# AD5940.net
KiCad netlist of a schematic drawn in Altium Designer
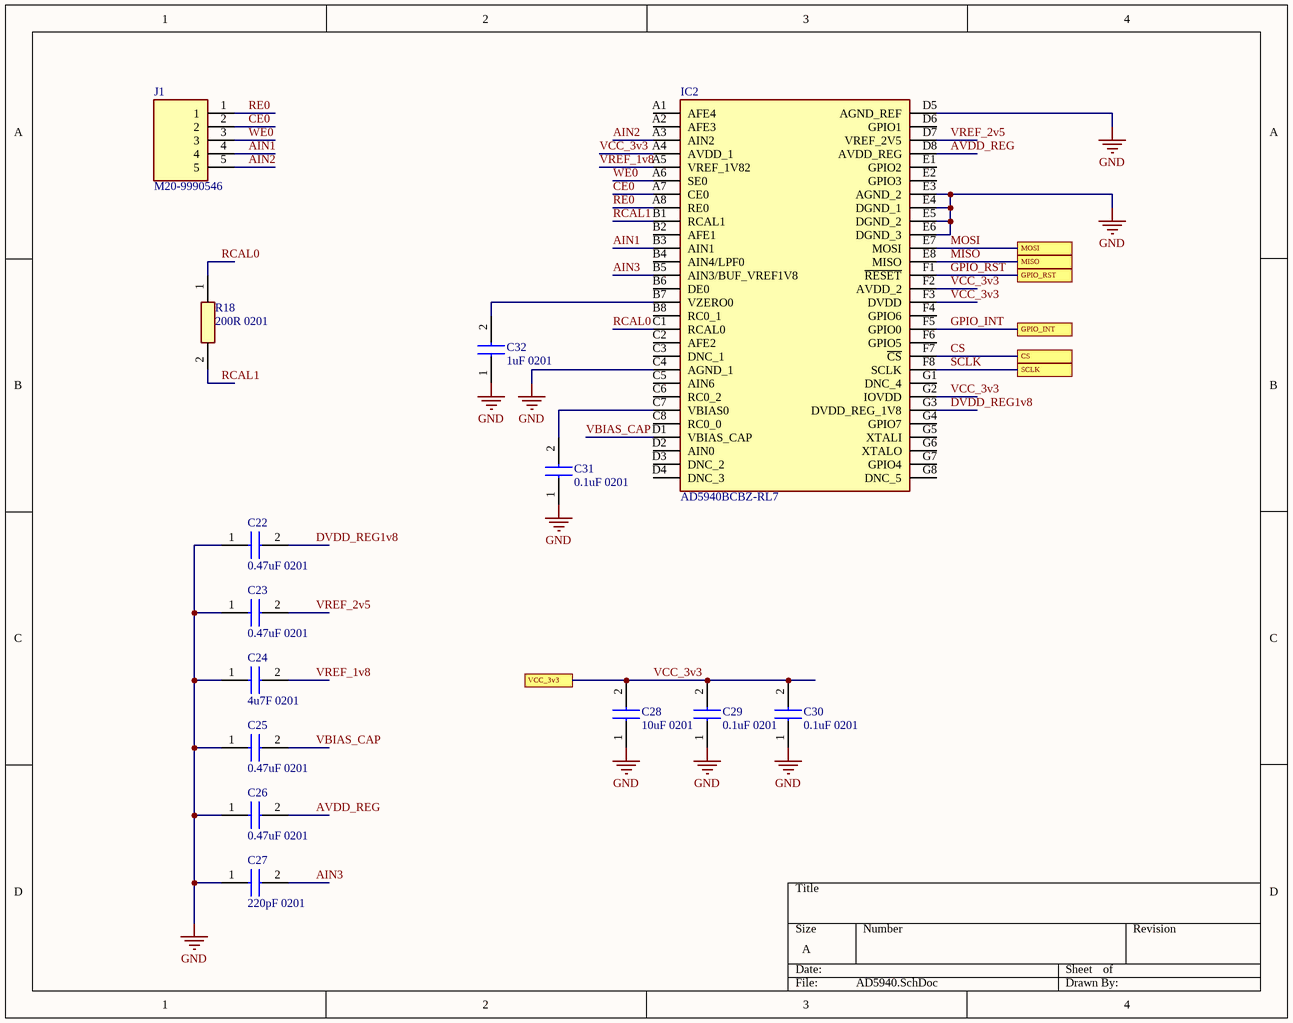
[diagram p0: AD5940.SchDoc]

(export (version "E")
  (design (tool "Eeschema 10.0.6"))
  (components
    (comp (ref "C22")
      (value "0.47uF 0201")
      (footprint "SamacSys:CAPC0603X33N")
      (description "Capacitor")
      (fields
        (field (name "MANUFACTURER_PART_NUMBER") "02013A0R5BAT2A")
        (field (name "MOUSER PART NUMBER") "581-02013A0R5BAT2A")
      )
      (libsource (lib "*") (part "02013A0R5BAT2A"))
    )
    (comp (ref "C23")
      (value "0.47uF 0201")
      (footprint "SamacSys:CAPC0603X33N")
      (description "Capacitor")
      (fields
        (field (name "MANUFACTURER_PART_NUMBER") "02013A0R5BAT2A")
        (field (name "MOUSER PART NUMBER") "581-02013A0R5BAT2A")
      )
      (libsource (lib "*") (part "02013A0R5BAT2A"))
    )
    (comp (ref "C24")
      (value "4u7F 0201")
      (footprint "SamacSys:CAPC0603X33N")
      (description "Capacitor")
      (fields
        (field (name "MANUFACTURER_PART_NUMBER") "02013A0R5BAT2A")
        (field (name "MOUSER PART NUMBER") "581-02013A0R5BAT2A")
      )
      (libsource (lib "*") (part "02013A0R5BAT2A"))
    )
    (comp (ref "C25")
      (value "0.47uF 0201")
      (footprint "SamacSys:CAPC0603X33N")
      (description "Capacitor")
      (fields
        (field (name "MANUFACTURER_PART_NUMBER") "02013A0R5BAT2A")
        (field (name "MOUSER PART NUMBER") "581-02013A0R5BAT2A")
      )
      (libsource (lib "*") (part "02013A0R5BAT2A"))
    )
    (comp (ref "C26")
      (value "0.47uF 0201")
      (footprint "SamacSys:CAPC0603X33N")
      (description "Capacitor")
      (fields
        (field (name "MANUFACTURER_PART_NUMBER") "02013A0R5BAT2A")
        (field (name "MOUSER PART NUMBER") "581-02013A0R5BAT2A")
      )
      (libsource (lib "*") (part "02013A0R5BAT2A"))
    )
    (comp (ref "C27")
      (value "220pF 0201")
      (footprint "SamacSys:CAPC0603X33N")
      (description "Capacitor")
      (fields
        (field (name "MANUFACTURER_PART_NUMBER") "02013A0R5BAT2A")
        (field (name "MOUSER PART NUMBER") "581-02013A0R5BAT2A")
      )
      (libsource (lib "*") (part "02013A0R5BAT2A"))
    )
    (comp (ref "C28")
      (value "10uF 0201")
      (footprint "SamacSys:CAPC0603X33N")
      (description "Capacitor")
      (fields
        (field (name "MANUFACTURER_PART_NUMBER") "02013A0R5BAT2A")
        (field (name "MOUSER PART NUMBER") "581-02013A0R5BAT2A")
      )
      (libsource (lib "*") (part "02013A0R5BAT2A"))
    )
    (comp (ref "C29")
      (value "0.1uF 0201")
      (footprint "SamacSys:CAPC0603X33N")
      (description "Capacitor")
      (fields
        (field (name "MANUFACTURER_PART_NUMBER") "02013A0R5BAT2A")
        (field (name "MOUSER PART NUMBER") "581-02013A0R5BAT2A")
      )
      (libsource (lib "*") (part "02013A0R5BAT2A"))
    )
    (comp (ref "C30")
      (value "0.1uF 0201")
      (footprint "SamacSys:CAPC0603X33N")
      (description "Capacitor")
      (fields
        (field (name "MANUFACTURER_PART_NUMBER") "02013A0R5BAT2A")
        (field (name "MOUSER PART NUMBER") "581-02013A0R5BAT2A")
      )
      (libsource (lib "*") (part "02013A0R5BAT2A"))
    )
    (comp (ref "C31")
      (value "0.1uF 0201")
      (footprint "SamacSys:CAPC0603X33N")
      (description "Capacitor")
      (fields
        (field (name "MANUFACTURER_PART_NUMBER") "02013A0R5BAT2A")
        (field (name "MOUSER PART NUMBER") "581-02013A0R5BAT2A")
      )
      (libsource (lib "*") (part "02013A0R5BAT2A"))
    )
    (comp (ref "C32")
      (value "1uF 0201")
      (footprint "SamacSys:CAPC0603X33N")
      (description "Capacitor")
      (fields
        (field (name "MANUFACTURER_PART_NUMBER") "02013A0R5BAT2A")
        (field (name "MOUSER PART NUMBER") "581-02013A0R5BAT2A")
      )
      (libsource (lib "*") (part "02013A0R5BAT2A"))
    )
    (comp (ref "IC2")
      (value "AD5940BCBZ-RL7")
      (footprint "SamacSys:BGA56C40P8X7_416X356X55")
      (description "Integrated Circuit")
      (fields (field (name "MOUSER PART NUMBER") "584-AD5940BCBZ-RL7"))
      (libsource (lib "*") (part "AD5940BCBZ-RL7"))
    )
    (comp (ref "J1")
      (value "M20-9990546")
      (footprint "SamacSys:HDRV5W64P0X254_1X5_1270X254X610P")
      (description "Connector")
      (fields (field (name "MOUSER PART NUMBER") "855-M20-9990546"))
      (libsource (lib "*") (part "M20-9990546"))
    )
    (comp (ref "R18")
      (value "200R 0201")
      (footprint "SamacSys:RESC0603X28N")
      (description "Resistor")
      (fields (field (name "MANUFACTURER_PART_NUMBER") "CPF0201D422RE1"))
      (libsource (lib "*") (part "CPF0201D422RE1"))
    )
  )
  (nets
    (net (code "1") (name "/AIN1") (class "Default")
      (node (ref "IC2") (pin "B3") (pinfunction "AIN1_B3") (pintype "passive"))
      (node (ref "J1") (pin "4") (pinfunction "4_4") (pintype "passive"))
    )
    (net (code "2") (name "/AIN2") (class "Default")
      (node (ref "IC2") (pin "A3") (pinfunction "AIN2_A3") (pintype "passive"))
      (node (ref "J1") (pin "5") (pinfunction "5_5") (pintype "passive"))
    )
    (net (code "3") (name "/AIN3") (class "Default")
      (node (ref "C27") (pin "2") (pinfunction "2_2") (pintype "passive"))
      (node (ref "IC2") (pin "B5") (pinfunction "AIN3/BUF_VREF1V8_B5") (pintype "passive"))
    )
    (net (code "4") (name "/AVDD_REG") (class "Default")
      (node (ref "C26") (pin "2") (pinfunction "2_2") (pintype "passive"))
      (node (ref "IC2") (pin "D8") (pinfunction "AVDD_REG_D8") (pintype "passive"))
    )
    (net (code "5") (name "/CE0") (class "Default")
      (node (ref "IC2") (pin "A7") (pinfunction "CE0_A7") (pintype "passive"))
      (node (ref "J1") (pin "2") (pinfunction "2_2") (pintype "passive"))
    )
    (net (code "6") (name "/CS") (class "Default")
      (node (ref "IC2") (pin "F7") (pinfunction "~{CS}_F7") (pintype "passive"))
    )
    (net (code "7") (name "/DVDD_REG1v8") (class "Default")
      (node (ref "C22") (pin "2") (pinfunction "2_2") (pintype "passive"))
      (node (ref "IC2") (pin "G3") (pinfunction "DVDD_REG_1V8_G3") (pintype "passive"))
    )
    (net (code "8") (name "/GPIO_INT") (class "Default")
      (node (ref "IC2") (pin "F5") (pinfunction "GPIO0_F5") (pintype "passive"))
    )
    (net (code "9") (name "/GPIO_RST") (class "Default")
      (node (ref "IC2") (pin "F1") (pinfunction "~{RESET}_F1") (pintype "passive"))
    )
    (net (code "10") (name "/MISO") (class "Default")
      (node (ref "IC2") (pin "E8") (pinfunction "MISO_E8") (pintype "passive"))
    )
    (net (code "11") (name "/MOSI") (class "Default")
      (node (ref "IC2") (pin "E7") (pinfunction "MOSI_E7") (pintype "passive"))
    )
    (net (code "12") (name "/RCAL0") (class "Default")
      (node (ref "IC2") (pin "C1") (pinfunction "RCAL0_C1") (pintype "passive"))
      (node (ref "R18") (pin "1") (pinfunction "1_1") (pintype "passive"))
    )
    (net (code "13") (name "/RCAL1") (class "Default")
      (node (ref "IC2") (pin "B1") (pinfunction "RCAL1_B1") (pintype "passive"))
      (node (ref "R18") (pin "2") (pinfunction "2_2") (pintype "passive"))
    )
    (net (code "14") (name "/RE0") (class "Default")
      (node (ref "IC2") (pin "A8") (pinfunction "RE0_A8") (pintype "passive"))
      (node (ref "J1") (pin "1") (pinfunction "1_1") (pintype "passive"))
    )
    (net (code "15") (name "/SCLK") (class "Default")
      (node (ref "IC2") (pin "F8") (pinfunction "SCLK_F8") (pintype "passive"))
    )
    (net (code "16") (name "/VBIAS_CAP") (class "Default")
      (node (ref "C25") (pin "2") (pinfunction "2_2") (pintype "passive"))
      (node (ref "IC2") (pin "D1") (pinfunction "VBIAS_CAP_D1") (pintype "passive"))
    )
    (net (code "17") (name "/VCC_3v3") (class "Default")
      (node (ref "C28") (pin "2") (pinfunction "2_2") (pintype "passive"))
      (node (ref "C29") (pin "2") (pinfunction "2_2") (pintype "passive"))
      (node (ref "C30") (pin "2") (pinfunction "2_2") (pintype "passive"))
      (node (ref "IC2") (pin "A4") (pinfunction "AVDD_1_A4") (pintype "passive"))
      (node (ref "IC2") (pin "F2") (pinfunction "AVDD_2_F2") (pintype "passive"))
      (node (ref "IC2") (pin "F3") (pinfunction "DVDD_F3") (pintype "passive"))
      (node (ref "IC2") (pin "G2") (pinfunction "IOVDD_G2") (pintype "passive"))
    )
    (net (code "18") (name "/VREF_1v8") (class "Default")
      (node (ref "C24") (pin "2") (pinfunction "2_2") (pintype "passive"))
      (node (ref "IC2") (pin "A5") (pinfunction "VREF_1V82_A5") (pintype "passive"))
    )
    (net (code "19") (name "/VREF_2v5") (class "Default")
      (node (ref "C23") (pin "2") (pinfunction "2_2") (pintype "passive"))
      (node (ref "IC2") (pin "D7") (pinfunction "VREF_2V5_D7") (pintype "passive"))
    )
    (net (code "20") (name "/WE0") (class "Default")
      (node (ref "IC2") (pin "A6") (pinfunction "SE0_A6") (pintype "passive"))
      (node (ref "J1") (pin "3") (pinfunction "3_3") (pintype "passive"))
    )
    (net (code "21") (name "GND") (class "Default")
      (node (ref "C22") (pin "1") (pinfunction "1_1") (pintype "passive"))
      (node (ref "C23") (pin "1") (pinfunction "1_1") (pintype "passive"))
      (node (ref "C24") (pin "1") (pinfunction "1_1") (pintype "passive"))
      (node (ref "C25") (pin "1") (pinfunction "1_1") (pintype "passive"))
      (node (ref "C26") (pin "1") (pinfunction "1_1") (pintype "passive"))
      (node (ref "C27") (pin "1") (pinfunction "1_1") (pintype "passive"))
      (node (ref "C28") (pin "1") (pinfunction "1_1") (pintype "passive"))
      (node (ref "C29") (pin "1") (pinfunction "1_1") (pintype "passive"))
      (node (ref "C30") (pin "1") (pinfunction "1_1") (pintype "passive"))
      (node (ref "C31") (pin "1") (pinfunction "1_1") (pintype "passive"))
      (node (ref "C32") (pin "1") (pinfunction "1_1") (pintype "passive"))
      (node (ref "IC2") (pin "C4") (pinfunction "AGND_1_C4") (pintype "passive"))
      (node (ref "IC2") (pin "D5") (pinfunction "AGND_REF_D5") (pintype "passive"))
      (node (ref "IC2") (pin "E3") (pinfunction "AGND_2_E3") (pintype "passive"))
      (node (ref "IC2") (pin "E4") (pinfunction "DGND_1_E4") (pintype "passive"))
      (node (ref "IC2") (pin "E5") (pinfunction "DGND_2_E5") (pintype "passive"))
      (node (ref "IC2") (pin "E6") (pinfunction "DGND_3_E6") (pintype "passive"))
    )
    (net (code "22") (name "Net-(IC2-VBIAS0)") (class "Default")
      (node (ref "C31") (pin "2") (pinfunction "2_2") (pintype "passive"))
      (node (ref "IC2") (pin "C7") (pinfunction "VBIAS0_C7") (pintype "passive"))
    )
    (net (code "23") (name "Net-(IC2-VZERO0)") (class "Default")
      (node (ref "C32") (pin "2") (pinfunction "2_2") (pintype "passive"))
      (node (ref "IC2") (pin "B7") (pinfunction "VZERO0_B7") (pintype "passive"))
    )
    (net (code "24") (name "unconnected-(IC2-AFE1-PadB2)") (class "Default")
      (node (ref "IC2") (pin "B2") (pinfunction "AFE1_B2") (pintype "passive"))
    )
    (net (code "25") (name "unconnected-(IC2-AFE2-PadC2)") (class "Default")
      (node (ref "IC2") (pin "C2") (pinfunction "AFE2_C2") (pintype "passive"))
    )
    (net (code "26") (name "unconnected-(IC2-AFE3-PadA2)") (class "Default")
      (node (ref "IC2") (pin "A2") (pinfunction "AFE3_A2") (pintype "passive"))
    )
    (net (code "27") (name "unconnected-(IC2-AFE4-PadA1)") (class "Default")
      (node (ref "IC2") (pin "A1") (pinfunction "AFE4_A1") (pintype "passive"))
    )
    (net (code "28") (name "unconnected-(IC2-AIN0-PadD2)") (class "Default")
      (node (ref "IC2") (pin "D2") (pinfunction "AIN0_D2") (pintype "passive"))
    )
    (net (code "29") (name "unconnected-(IC2-AIN4{slash}LPF0-PadB4)") (class "Default")
      (node (ref "IC2") (pin "B4") (pinfunction "AIN4/LPF0_B4") (pintype "passive"))
    )
    (net (code "30") (name "unconnected-(IC2-AIN6-PadC5)") (class "Default")
      (node (ref "IC2") (pin "C5") (pinfunction "AIN6_C5") (pintype "passive"))
    )
    (net (code "31") (name "unconnected-(IC2-DE0-PadB6)") (class "Default")
      (node (ref "IC2") (pin "B6") (pinfunction "DE0_B6") (pintype "passive"))
    )
    (net (code "32") (name "unconnected-(IC2-DNC_1-PadC3)") (class "Default")
      (node (ref "IC2") (pin "C3") (pinfunction "DNC_1_C3") (pintype "passive"))
    )
    (net (code "33") (name "unconnected-(IC2-DNC_2-PadD3)") (class "Default")
      (node (ref "IC2") (pin "D3") (pinfunction "DNC_2_D3") (pintype "passive"))
    )
    (net (code "34") (name "unconnected-(IC2-DNC_3-PadD4)") (class "Default")
      (node (ref "IC2") (pin "D4") (pinfunction "DNC_3_D4") (pintype "passive"))
    )
    (net (code "35") (name "unconnected-(IC2-DNC_4-PadG1)") (class "Default")
      (node (ref "IC2") (pin "G1") (pinfunction "DNC_4_G1") (pintype "passive"))
    )
    (net (code "36") (name "unconnected-(IC2-DNC_5-PadG8)") (class "Default")
      (node (ref "IC2") (pin "G8") (pinfunction "DNC_5_G8") (pintype "passive"))
    )
    (net (code "37") (name "unconnected-(IC2-GPIO1-PadD6)") (class "Default")
      (node (ref "IC2") (pin "D6") (pinfunction "GPIO1_D6") (pintype "passive"))
    )
    (net (code "38") (name "unconnected-(IC2-GPIO2-PadE1)") (class "Default")
      (node (ref "IC2") (pin "E1") (pinfunction "GPIO2_E1") (pintype "passive"))
    )
    (net (code "39") (name "unconnected-(IC2-GPIO3-PadE2)") (class "Default")
      (node (ref "IC2") (pin "E2") (pinfunction "GPIO3_E2") (pintype "passive"))
    )
    (net (code "40") (name "unconnected-(IC2-GPIO4-PadG7)") (class "Default")
      (node (ref "IC2") (pin "G7") (pinfunction "GPIO4_G7") (pintype "passive"))
    )
    (net (code "41") (name "unconnected-(IC2-GPIO5-PadF6)") (class "Default")
      (node (ref "IC2") (pin "F6") (pinfunction "GPIO5_F6") (pintype "passive"))
    )
    (net (code "42") (name "unconnected-(IC2-GPIO6-PadF4)") (class "Default")
      (node (ref "IC2") (pin "F4") (pinfunction "GPIO6_F4") (pintype "passive"))
    )
    (net (code "43") (name "unconnected-(IC2-GPIO7-PadG4)") (class "Default")
      (node (ref "IC2") (pin "G4") (pinfunction "GPIO7_G4") (pintype "passive"))
    )
    (net (code "44") (name "unconnected-(IC2-RC0_0-PadC8)") (class "Default")
      (node (ref "IC2") (pin "C8") (pinfunction "RC0_0_C8") (pintype "passive"))
    )
    (net (code "45") (name "unconnected-(IC2-RC0_1-PadB8)") (class "Default")
      (node (ref "IC2") (pin "B8") (pinfunction "RC0_1_B8") (pintype "passive"))
    )
    (net (code "46") (name "unconnected-(IC2-RC0_2-PadC6)") (class "Default")
      (node (ref "IC2") (pin "C6") (pinfunction "RC0_2_C6") (pintype "passive"))
    )
    (net (code "47") (name "unconnected-(IC2-XTALI-PadG5)") (class "Default")
      (node (ref "IC2") (pin "G5") (pinfunction "XTALI_G5") (pintype "passive"))
    )
    (net (code "48") (name "unconnected-(IC2-XTALO-PadG6)") (class "Default")
      (node (ref "IC2") (pin "G6") (pinfunction "XTALO_G6") (pintype "passive"))
    )
  )
)
